# breadboard_rev04.net
KiCad netlist of a schematic drawn in EAGLE
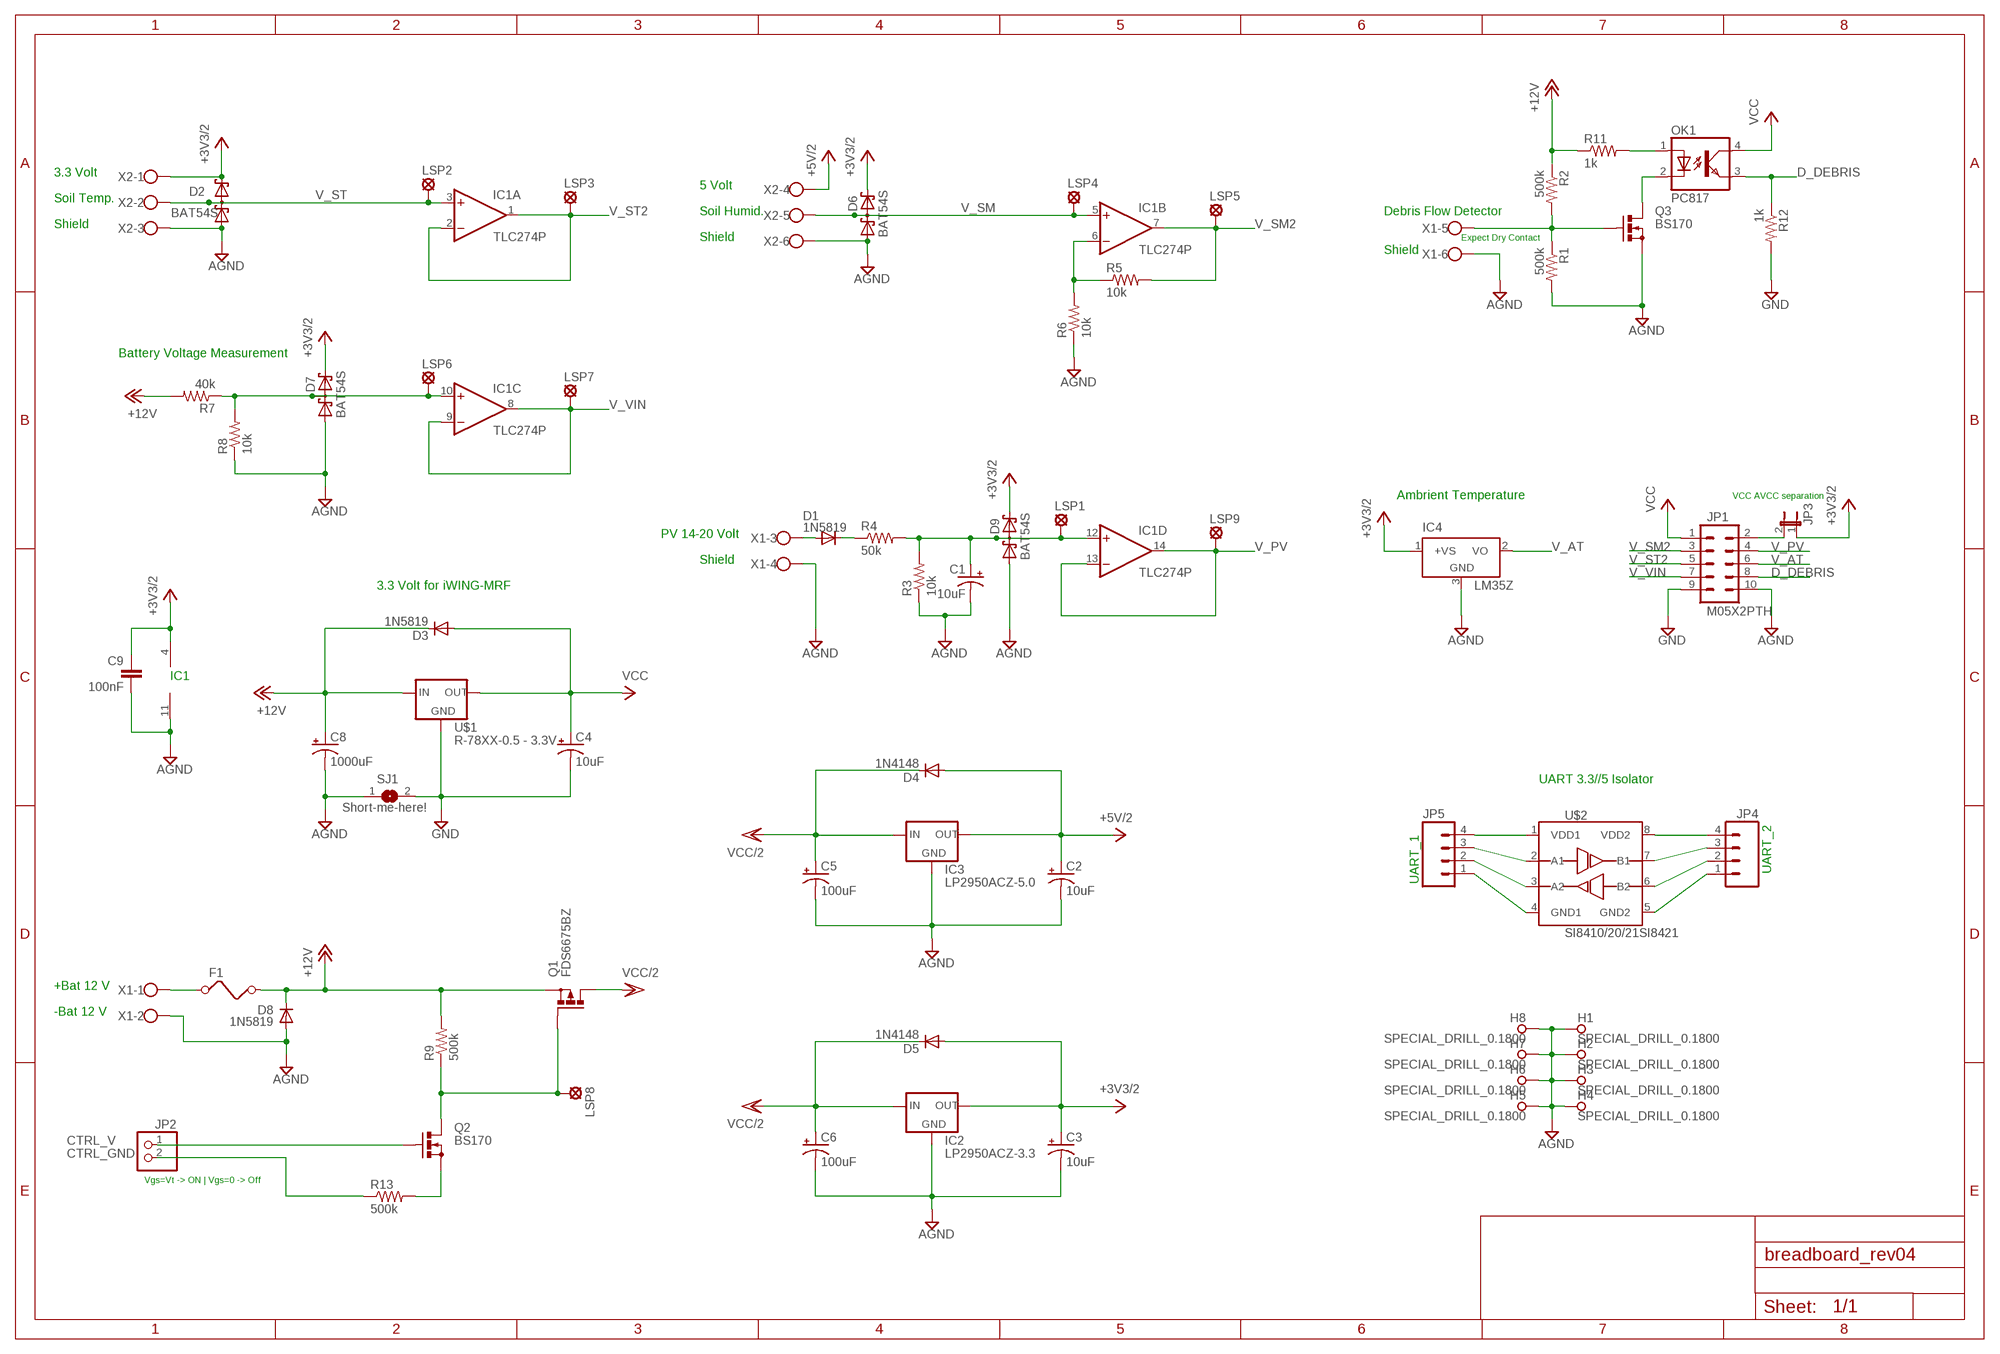
[diagram p0: schematic, sheet 1]

(export (version "E")
  (design (tool "Eeschema 10.0.6"))
  (components
    (comp (ref "C1")
      (value "10uF")
      (footprint "eagle-import:RCL_E2,5-7")
      (libsource (lib "eagle-import") (part "RCL_CPOL-USE2.5-7"))
    )
    (comp (ref "C2")
      (value "10uF")
      (footprint "eagle-import:RCL_E2,5-7")
      (libsource (lib "eagle-import") (part "RCL_CPOL-USE2.5-7"))
    )
    (comp (ref "C3")
      (value "10uF")
      (footprint "eagle-import:RCL_E2,5-7")
      (libsource (lib "eagle-import") (part "RCL_CPOL-USE2.5-7"))
    )
    (comp (ref "C4")
      (value "10uF")
      (footprint "eagle-import:RCL_E2,5-7")
      (libsource (lib "eagle-import") (part "RCL_CPOL-USE2.5-7"))
    )
    (comp (ref "C5")
      (value "100uF")
      (footprint "eagle-import:RCL_E2,5-7")
      (libsource (lib "eagle-import") (part "RCL_CPOL-USE2.5-7"))
    )
    (comp (ref "C6")
      (value "100uF")
      (footprint "eagle-import:RCL_E2,5-7")
      (libsource (lib "eagle-import") (part "RCL_CPOL-USE2.5-7"))
    )
    (comp (ref "C8")
      (value "1000uF")
      (footprint "eagle-import:RCL_E5-13")
      (libsource (lib "eagle-import") (part "RCL_CPOL-USE5-13"))
    )
    (comp (ref "C9")
      (value "100nF")
      (footprint "eagle-import:RCL_C050-025X075")
      (libsource (lib "eagle-import") (part "RCL_C-EU050-025X075"))
    )
    (comp (ref "D1")
      (value "1N5819")
      (footprint "eagle-import:DO41-10")
      (libsource (lib "eagle-import") (part "1N5819"))
    )
    (comp (ref "D2")
      (value "BAT54S")
      (footprint "eagle-import:SOT23")
      (libsource (lib "eagle-import") (part "BAT54S"))
    )
    (comp (ref "D3")
      (value "1N5819")
      (footprint "eagle-import:DO41-10")
      (libsource (lib "eagle-import") (part "1N5819"))
    )
    (comp (ref "D4")
      (value "1N4148")
      (footprint "eagle-import:DO35-10")
      (libsource (lib "eagle-import") (part "1N4148"))
    )
    (comp (ref "D5")
      (value "1N4148")
      (footprint "eagle-import:DO35-10")
      (libsource (lib "eagle-import") (part "1N4148"))
    )
    (comp (ref "D6")
      (value "BAT54S")
      (footprint "eagle-import:SOT23")
      (libsource (lib "eagle-import") (part "BAT54S"))
    )
    (comp (ref "D7")
      (value "BAT54S")
      (footprint "eagle-import:SOT23")
      (libsource (lib "eagle-import") (part "BAT54S"))
    )
    (comp (ref "D8")
      (value "1N5819")
      (footprint "eagle-import:DO41-10")
      (libsource (lib "eagle-import") (part "1N5819"))
    )
    (comp (ref "D9")
      (value "BAT54S")
      (footprint "eagle-import:SOT23")
      (libsource (lib "eagle-import") (part "BAT54S"))
    )
    (comp (ref "F1")
      (value "FUSE")
      (footprint "eagle-import:FUSE")
      (libsource (lib "eagle-import") (part "FUSE"))
    )
    (comp (ref "H1")
      (value "SPECIAL_DRILL_0.1800")
      (footprint "eagle-import:PAD_0.1800")
      (libsource (lib "eagle-import") (part "SPECIAL_DRILL_0.1800"))
    )
    (comp (ref "H2")
      (value "SPECIAL_DRILL_0.1800")
      (footprint "eagle-import:PAD_0.1800")
      (libsource (lib "eagle-import") (part "SPECIAL_DRILL_0.1800"))
    )
    (comp (ref "H3")
      (value "SPECIAL_DRILL_0.1800")
      (footprint "eagle-import:PAD_0.1800")
      (libsource (lib "eagle-import") (part "SPECIAL_DRILL_0.1800"))
    )
    (comp (ref "H4")
      (value "SPECIAL_DRILL_0.1800")
      (footprint "eagle-import:PAD_0.1800")
      (libsource (lib "eagle-import") (part "SPECIAL_DRILL_0.1800"))
    )
    (comp (ref "H5")
      (value "SPECIAL_DRILL_0.1800")
      (footprint "eagle-import:PAD_0.1800")
      (libsource (lib "eagle-import") (part "SPECIAL_DRILL_0.1800"))
    )
    (comp (ref "H6")
      (value "SPECIAL_DRILL_0.1800")
      (footprint "eagle-import:PAD_0.1800")
      (libsource (lib "eagle-import") (part "SPECIAL_DRILL_0.1800"))
    )
    (comp (ref "H7")
      (value "SPECIAL_DRILL_0.1800")
      (footprint "eagle-import:PAD_0.1800")
      (libsource (lib "eagle-import") (part "SPECIAL_DRILL_0.1800"))
    )
    (comp (ref "H8")
      (value "SPECIAL_DRILL_0.1800")
      (footprint "eagle-import:PAD_0.1800")
      (libsource (lib "eagle-import") (part "SPECIAL_DRILL_0.1800"))
    )
    (comp (ref "IC1")
      (value "TLC274P")
      (footprint "eagle-import:DIL14")
      (libsource (lib "eagle-import") (part "TLC274P"))
    )
    (comp (ref "IC2")
      (value "LP2950ACZ-3.3")
      (footprint "eagle-import:TO92")
      (libsource (lib "eagle-import") (part "LP2950?ACZ-3.3"))
    )
    (comp (ref "IC3")
      (value "LP2950ACZ-5.0")
      (footprint "eagle-import:TO92")
      (libsource (lib "eagle-import") (part "LP2950?ACZ-5.0"))
    )
    (comp (ref "IC4")
      (value "LM35Z")
      (footprint "eagle-import:TO92")
      (libsource (lib "eagle-import") (part "LM35?Z"))
    )
    (comp (ref "JP1")
      (value "M05X2PTH")
      (footprint "eagle-import:AVR_ICSP")
      (libsource (lib "eagle-import") (part "M05X2PTH"))
    )
    (comp (ref "JP2")
      (value "PINHD-1X2")
      (footprint "eagle-import:1X02")
      (libsource (lib "eagle-import") (part "PINHD-1X2"))
    )
    (comp (ref "JP3")
      (value "JP1E")
      (footprint "eagle-import:JUMPER_JP1")
      (libsource (lib "eagle-import") (part "JP1E"))
    )
    (comp (ref "JP4")
      (value "M04POLAR")
      (footprint "eagle-import:MOLEX-1X4")
      (libsource (lib "eagle-import") (part "M04POLAR"))
    )
    (comp (ref "JP5")
      (value "M04POLAR")
      (footprint "eagle-import:MOLEX-1X4")
      (libsource (lib "eagle-import") (part "M04POLAR"))
    )
    (comp (ref "LSP1")
      (value "LSP13")
      (footprint "eagle-import:LSP13")
      (libsource (lib "eagle-import") (part "LSP13"))
    )
    (comp (ref "LSP2")
      (value "LSP13")
      (footprint "eagle-import:LSP13")
      (libsource (lib "eagle-import") (part "LSP13"))
    )
    (comp (ref "LSP3")
      (value "LSP13")
      (footprint "eagle-import:LSP13")
      (libsource (lib "eagle-import") (part "LSP13"))
    )
    (comp (ref "LSP4")
      (value "LSP13")
      (footprint "eagle-import:LSP13")
      (libsource (lib "eagle-import") (part "LSP13"))
    )
    (comp (ref "LSP5")
      (value "LSP13")
      (footprint "eagle-import:LSP13")
      (libsource (lib "eagle-import") (part "LSP13"))
    )
    (comp (ref "LSP6")
      (value "LSP13")
      (footprint "eagle-import:LSP13")
      (libsource (lib "eagle-import") (part "LSP13"))
    )
    (comp (ref "LSP7")
      (value "LSP13")
      (footprint "eagle-import:LSP13")
      (libsource (lib "eagle-import") (part "LSP13"))
    )
    (comp (ref "LSP8")
      (value "LSP13")
      (footprint "eagle-import:LSP13")
      (libsource (lib "eagle-import") (part "LSP13"))
    )
    (comp (ref "LSP9")
      (value "LSP13")
      (footprint "eagle-import:LSP13")
      (libsource (lib "eagle-import") (part "LSP13"))
    )
    (comp (ref "OK1")
      (value "PC817")
      (footprint "eagle-import:DIL04")
      (fields (field (name "MPN") "PC817X4J000F"))
      (libsource (lib "eagle-import") (part "PC817"))
    )
    (comp (ref "Q1")
      (value "FDS6675BZ")
      (footprint "eagle-import:SO-08")
      (libsource (lib "eagle-import") (part "P-MOSFET-SO8"))
    )
    (comp (ref "Q2")
      (value "BS170")
      (footprint "eagle-import:SOT54E")
      (libsource (lib "eagle-import") (part "BS170"))
    )
    (comp (ref "Q3")
      (value "BS170")
      (footprint "eagle-import:SOT54E")
      (libsource (lib "eagle-import") (part "BS170"))
    )
    (comp (ref "R1")
      (value "500k")
      (footprint "eagle-import:RCL_0204_7")
      (libsource (lib "eagle-import") (part "RCL_R-US_0204/7"))
    )
    (comp (ref "R2")
      (value "500k")
      (footprint "eagle-import:RCL_0204_7")
      (libsource (lib "eagle-import") (part "RCL_R-US_0204/7"))
    )
    (comp (ref "R3")
      (value "10k")
      (footprint "eagle-import:RCL_0204_7")
      (libsource (lib "eagle-import") (part "RCL_R-US_0204/7"))
    )
    (comp (ref "R4")
      (value "50k")
      (footprint "eagle-import:RCL_0204_7")
      (libsource (lib "eagle-import") (part "RCL_R-US_0204/7"))
    )
    (comp (ref "R5")
      (value "10k")
      (footprint "eagle-import:RCL_0204_7")
      (libsource (lib "eagle-import") (part "RCL_R-US_0204/7"))
    )
    (comp (ref "R6")
      (value "10k")
      (footprint "eagle-import:RCL_0204_7")
      (libsource (lib "eagle-import") (part "RCL_R-US_0204/7"))
    )
    (comp (ref "R7")
      (value "40k")
      (footprint "eagle-import:RCL_0204_7")
      (libsource (lib "eagle-import") (part "RCL_R-US_0204/7"))
    )
    (comp (ref "R8")
      (value "10k")
      (footprint "eagle-import:RCL_0204_7")
      (libsource (lib "eagle-import") (part "RCL_R-US_0204/7"))
    )
    (comp (ref "R9")
      (value "500k")
      (footprint "eagle-import:RCL_0204_7")
      (libsource (lib "eagle-import") (part "RCL_R-US_0204/7"))
    )
    (comp (ref "R11")
      (value "1k")
      (footprint "eagle-import:RCL_0204_7")
      (libsource (lib "eagle-import") (part "RCL_R-US_0204/7"))
    )
    (comp (ref "R12")
      (value "1k")
      (footprint "eagle-import:RCL_0204_7")
      (libsource (lib "eagle-import") (part "RCL_R-US_0204/7"))
    )
    (comp (ref "R13")
      (value "500k")
      (footprint "eagle-import:RCL_0204_7")
      (libsource (lib "eagle-import") (part "RCL_R-US_0204/7"))
    )
    (comp (ref "SJ1")
      (value "Short-me-here!")
      (footprint "eagle-import:SJ")
      (libsource (lib "eagle-import") (part "SJ"))
    )
    (comp (ref "U$1")
      (value "R-78XX-0.5 - 3.3V")
      (footprint "eagle-import:SIP3")
      (libsource (lib "eagle-import") (part "R-78XX-0.5"))
    )
    (comp (ref "U$2")
      (value "SI8410/20/21SI8421")
      (footprint "eagle-import:SO-08")
      (libsource (lib "eagle-import") (part "SI8410/20/21SI8421"))
    )
    (comp (ref "X1")
      (value "5EHDRC-6P")
      (footprint "eagle-import:5EHDRC-6P")
      (libsource (lib "eagle-import") (part "5EHDRC-6P"))
    )
    (comp (ref "X2")
      (value "5EHDRC-6P")
      (footprint "eagle-import:5EHDRC-6P")
      (libsource (lib "eagle-import") (part "5EHDRC-6P"))
    )
  )
  (nets
    (net (code "1") (name "+3V3{slash}2") (class "Default")
      (node (ref "C3") (pin "+") (pinfunction "+_+") (pintype "passive"))
      (node (ref "C9") (pin "1") (pinfunction "1_1") (pintype "passive"))
      (node (ref "D2") (pin "3") (pinfunction "C2_3") (pintype "passive"))
      (node (ref "D5") (pin "A") (pinfunction "A_A") (pintype "passive"))
      (node (ref "D6") (pin "3") (pinfunction "C2_3") (pintype "passive"))
      (node (ref "D7") (pin "3") (pinfunction "C2_3") (pintype "passive"))
      (node (ref "D9") (pin "3") (pinfunction "C2_3") (pintype "passive"))
      (node (ref "IC1") (pin "4") (pinfunction "V+_4") (pintype "power_in"))
      (node (ref "IC2") (pin "1") (pinfunction "OUT_1") (pintype "passive"))
      (node (ref "IC4") (pin "1") (pinfunction "+VS_1") (pintype "input"))
      (node (ref "JP3") (pin "1") (pinfunction "1_1") (pintype "passive"))
      (node (ref "X2") (pin "1") (pinfunction "KL_1") (pintype "passive"))
    )
    (net (code "2") (name "+5V{slash}2") (class "Default")
      (node (ref "C2") (pin "+") (pinfunction "+_+") (pintype "passive"))
      (node (ref "D4") (pin "A") (pinfunction "A_A") (pintype "passive"))
      (node (ref "IC3") (pin "1") (pinfunction "OUT_1") (pintype "passive"))
      (node (ref "X2") (pin "4") (pinfunction "KL_4") (pintype "passive"))
    )
    (net (code "3") (name "+12V") (class "Default")
      (node (ref "C8") (pin "+") (pinfunction "+_+") (pintype "passive"))
      (node (ref "D3") (pin "C") (pinfunction "C_C") (pintype "passive"))
      (node (ref "D8") (pin "C") (pinfunction "C_C") (pintype "passive"))
      (node (ref "F1") (pin "2") (pinfunction "2_2") (pintype "passive"))
      (node (ref "Q1") (pin "1") (pinfunction "S_1") (pintype "passive"))
      (node (ref "Q1") (pin "2") (pinfunction "S_2") (pintype "passive"))
      (node (ref "Q1") (pin "3") (pinfunction "S_3") (pintype "passive"))
      (node (ref "R11") (pin "1") (pinfunction "1_1") (pintype "passive"))
      (node (ref "R2") (pin "1") (pinfunction "1_1") (pintype "passive"))
      (node (ref "R7") (pin "2") (pinfunction "2_2") (pintype "passive"))
      (node (ref "R9") (pin "2") (pinfunction "2_2") (pintype "passive"))
      (node (ref "U$1") (pin "1") (pinfunction "IN_1") (pintype "input"))
    )
    (net (code "4") (name "/CTRL_GND") (class "Default")
      (node (ref "JP2") (pin "2") (pinfunction "2_2") (pintype "passive"))
      (node (ref "R13") (pin "1") (pinfunction "1_1") (pintype "passive"))
    )
    (net (code "5") (name "/CTRL_V") (class "Default")
      (node (ref "JP2") (pin "1") (pinfunction "1_1") (pintype "passive"))
      (node (ref "Q2") (pin "G") (pinfunction "G_G") (pintype "passive"))
    )
    (net (code "6") (name "/D_DEBRIS") (class "Default")
      (node (ref "JP1") (pin "8") (pinfunction "8_8") (pintype "passive"))
      (node (ref "OK1") (pin "3") (pinfunction "EMIT_3") (pintype "passive"))
      (node (ref "R12") (pin "1") (pinfunction "1_1") (pintype "passive"))
    )
    (net (code "7") (name "/V_AT") (class "Default")
      (node (ref "IC4") (pin "2") (pinfunction "VO_2") (pintype "output"))
      (node (ref "JP1") (pin "6") (pinfunction "6_6") (pintype "passive"))
    )
    (net (code "8") (name "/V_PV") (class "Default")
      (node (ref "IC1") (pin "13") (pinfunction "-IN_13") (pintype "input"))
      (node (ref "IC1") (pin "14") (pinfunction "OUT_14") (pintype "output"))
      (node (ref "JP1") (pin "4") (pinfunction "4_4") (pintype "passive"))
      (node (ref "LSP9") (pin "MP") (pinfunction "MP_MP") (pintype "passive"))
    )
    (net (code "9") (name "/V_SM") (class "Default")
      (node (ref "D6") (pin "2") (pinfunction "C1A2_2") (pintype "passive"))
      (node (ref "IC1") (pin "5") (pinfunction "+IN_5") (pintype "input"))
      (node (ref "LSP4") (pin "MP") (pinfunction "MP_MP") (pintype "passive"))
      (node (ref "X2") (pin "5") (pinfunction "KL_5") (pintype "passive"))
    )
    (net (code "10") (name "/V_SM2") (class "Default")
      (node (ref "IC1") (pin "7") (pinfunction "OUT_7") (pintype "output"))
      (node (ref "JP1") (pin "3") (pinfunction "3_3") (pintype "passive"))
      (node (ref "LSP5") (pin "MP") (pinfunction "MP_MP") (pintype "passive"))
      (node (ref "R5") (pin "2") (pinfunction "2_2") (pintype "passive"))
    )
    (net (code "11") (name "/V_ST") (class "Default")
      (node (ref "D2") (pin "2") (pinfunction "C1A2_2") (pintype "passive"))
      (node (ref "IC1") (pin "3") (pinfunction "+IN_3") (pintype "input"))
      (node (ref "LSP2") (pin "MP") (pinfunction "MP_MP") (pintype "passive"))
      (node (ref "X2") (pin "2") (pinfunction "KL_2") (pintype "passive"))
    )
    (net (code "12") (name "/V_ST2") (class "Default")
      (node (ref "IC1") (pin "1") (pinfunction "OUT_1") (pintype "output"))
      (node (ref "IC1") (pin "2") (pinfunction "-IN_2") (pintype "input"))
      (node (ref "JP1") (pin "5") (pinfunction "5_5") (pintype "passive"))
      (node (ref "LSP3") (pin "MP") (pinfunction "MP_MP") (pintype "passive"))
    )
    (net (code "13") (name "/V_VIN") (class "Default")
      (node (ref "IC1") (pin "8") (pinfunction "OUT_8") (pintype "output"))
      (node (ref "IC1") (pin "9") (pinfunction "-IN_9") (pintype "input"))
      (node (ref "JP1") (pin "7") (pinfunction "7_7") (pintype "passive"))
      (node (ref "LSP7") (pin "MP") (pinfunction "MP_MP") (pintype "passive"))
    )
    (net (code "14") (name "AGND") (class "Default")
      (node (ref "C1") (pin "-") (pinfunction "-_-") (pintype "passive"))
      (node (ref "C2") (pin "-") (pinfunction "-_-") (pintype "passive"))
      (node (ref "C3") (pin "-") (pinfunction "-_-") (pintype "passive"))
      (node (ref "C5") (pin "-") (pinfunction "-_-") (pintype "passive"))
      (node (ref "C6") (pin "-") (pinfunction "-_-") (pintype "passive"))
      (node (ref "C8") (pin "-") (pinfunction "-_-") (pintype "passive"))
      (node (ref "C9") (pin "2") (pinfunction "2_2") (pintype "passive"))
      (node (ref "D2") (pin "1") (pinfunction "A1_1") (pintype "passive"))
      (node (ref "D6") (pin "1") (pinfunction "A1_1") (pintype "passive"))
      (node (ref "D7") (pin "1") (pinfunction "A1_1") (pintype "passive"))
      (node (ref "D8") (pin "A") (pinfunction "A_A") (pintype "passive"))
      (node (ref "D9") (pin "1") (pinfunction "A1_1") (pintype "passive"))
      (node (ref "H1") (pin "1") (pinfunction "1_1") (pintype "passive"))
      (node (ref "H2") (pin "1") (pinfunction "1_1") (pintype "passive"))
      (node (ref "H3") (pin "1") (pinfunction "1_1") (pintype "passive"))
      (node (ref "H4") (pin "1") (pinfunction "1_1") (pintype "passive"))
      (node (ref "H5") (pin "1") (pinfunction "1_1") (pintype "passive"))
      (node (ref "H6") (pin "1") (pinfunction "1_1") (pintype "passive"))
      (node (ref "H7") (pin "1") (pinfunction "1_1") (pintype "passive"))
      (node (ref "H8") (pin "1") (pinfunction "1_1") (pintype "passive"))
      (node (ref "IC1") (pin "11") (pinfunction "V-_11") (pintype "power_in"))
      (node (ref "IC2") (pin "2") (pinfunction "GND_2") (pintype "input"))
      (node (ref "IC3") (pin "2") (pinfunction "GND_2") (pintype "input"))
      (node (ref "IC4") (pin "3") (pinfunction "GND_3") (pintype "power_in"))
      (node (ref "JP1") (pin "10") (pinfunction "10_10") (pintype "passive"))
      (node (ref "Q3") (pin "S") (pinfunction "S_S") (pintype "passive"))
      (node (ref "R1") (pin "2") (pinfunction "2_2") (pintype "passive"))
      (node (ref "R3") (pin "1") (pinfunction "1_1") (pintype "passive"))
      (node (ref "R6") (pin "1") (pinfunction "1_1") (pintype "passive"))
      (node (ref "R8") (pin "1") (pinfunction "1_1") (pintype "passive"))
      (node (ref "SJ1") (pin "1") (pinfunction "1_1") (pintype "passive"))
      (node (ref "X1") (pin "2") (pinfunction "KL_2") (pintype "passive"))
      (node (ref "X1") (pin "4") (pinfunction "KL_4") (pintype "passive"))
      (node (ref "X1") (pin "6") (pinfunction "KL_6") (pintype "passive"))
      (node (ref "X2") (pin "3") (pinfunction "KL_3") (pintype "passive"))
      (node (ref "X2") (pin "6") (pinfunction "KL_6") (pintype "passive"))
    )
    (net (code "15") (name "GND") (class "Default")
      (node (ref "C4") (pin "-") (pinfunction "-_-") (pintype "passive"))
      (node (ref "JP1") (pin "9") (pinfunction "9_9") (pintype "passive"))
      (node (ref "R12") (pin "2") (pinfunction "2_2") (pintype "passive"))
      (node (ref "SJ1") (pin "2") (pinfunction "2_2") (pintype "passive"))
      (node (ref "U$1") (pin "2") (pinfunction "GND_2") (pintype "input"))
    )
    (net (code "16") (name "Net-(D1-PadC)") (class "Default")
      (node (ref "D1") (pin "C") (pinfunction "C_C") (pintype "passive"))
      (node (ref "R4") (pin "1") (pinfunction "1_1") (pintype "passive"))
    )
    (net (code "17") (name "Net-(D7-C1A2)") (class "Default")
      (node (ref "D7") (pin "2") (pinfunction "C1A2_2") (pintype "passive"))
      (node (ref "IC1") (pin "10") (pinfunction "+IN_10") (pintype "input"))
      (node (ref "LSP6") (pin "MP") (pinfunction "MP_MP") (pintype "passive"))
      (node (ref "R7") (pin "1") (pinfunction "1_1") (pintype "passive"))
      (node (ref "R8") (pin "2") (pinfunction "2_2") (pintype "passive"))
    )
    (net (code "18") (name "Net-(D9-C1A2)") (class "Default")
      (node (ref "C1") (pin "+") (pinfunction "+_+") (pintype "passive"))
      (node (ref "D9") (pin "2") (pinfunction "C1A2_2") (pintype "passive"))
      (node (ref "IC1") (pin "12") (pinfunction "+IN_12") (pintype "input"))
      (node (ref "LSP1") (pin "MP") (pinfunction "MP_MP") (pintype "passive"))
      (node (ref "R3") (pin "2") (pinfunction "2_2") (pintype "passive"))
      (node (ref "R4") (pin "2") (pinfunction "2_2") (pintype "passive"))
    )
    (net (code "19") (name "Net-(IC1B--IN)") (class "Default")
      (node (ref "IC1") (pin "6") (pinfunction "-IN_6") (pintype "input"))
      (node (ref "R5") (pin "1") (pinfunction "1_1") (pintype "passive"))
      (node (ref "R6") (pin "2") (pinfunction "2_2") (pintype "passive"))
    )
    (net (code "20") (name "Net-(JP1-Pad2)") (class "Default")
      (node (ref "JP1") (pin "2") (pinfunction "2_2") (pintype "passive"))
      (node (ref "JP3") (pin "2") (pinfunction "2_2") (pintype "passive"))
    )
    (net (code "21") (name "Net-(OK1-A)") (class "Default")
      (node (ref "OK1") (pin "1") (pinfunction "A_1") (pintype "passive"))
      (node (ref "R11") (pin "2") (pinfunction "2_2") (pintype "passive"))
    )
    (net (code "22") (name "Net-(OK1-C)") (class "Default")
      (node (ref "OK1") (pin "2") (pinfunction "C_2") (pintype "passive"))
      (node (ref "Q3") (pin "D") (pinfunction "D_D") (pintype "passive"))
    )
    (net (code "23") (name "Net-(Q1-G)") (class "Default")
      (node (ref "LSP8") (pin "MP") (pinfunction "MP_MP") (pintype "passive"))
      (node (ref "Q1") (pin "4") (pinfunction "G_4") (pintype "passive"))
      (node (ref "Q2") (pin "D") (pinfunction "D_D") (pintype "passive"))
      (node (ref "R9") (pin "1") (pinfunction "1_1") (pintype "passive"))
    )
    (net (code "24") (name "Net-(Q2-PadS)") (class "Default")
      (node (ref "Q2") (pin "S") (pinfunction "S_S") (pintype "passive"))
      (node (ref "R13") (pin "2") (pinfunction "2_2") (pintype "passive"))
    )
    (net (code "25") (name "Net-(U$2-A1)") (class "Default")
      (node (ref "JP5") (pin "3") (pinfunction "3_3") (pintype "passive"))
      (node (ref "U$2") (pin "2") (pinfunction "A1_2") (pintype "input"))
    )
    (net (code "26") (name "Net-(U$2-A2)") (class "Default")
      (node (ref "JP5") (pin "2") (pinfunction "2_2") (pintype "passive"))
      (node (ref "U$2") (pin "3") (pinfunction "A2_3") (pintype "output"))
    )
    (net (code "27") (name "Net-(U$2-B1)") (class "Default")
      (node (ref "JP4") (pin "3") (pinfunction "3_3") (pintype "passive"))
      (node (ref "U$2") (pin "7") (pinfunction "B1_7") (pintype "output"))
    )
    (net (code "28") (name "Net-(U$2-B2)") (class "Default")
      (node (ref "JP4") (pin "2") (pinfunction "2_2") (pintype "passive"))
      (node (ref "U$2") (pin "6") (pinfunction "B2_6") (pintype "input"))
    )
    (net (code "29") (name "Net-(U$2-GND1)") (class "Default")
      (node (ref "JP5") (pin "1") (pinfunction "1_1") (pintype "passive"))
      (node (ref "U$2") (pin "4") (pinfunction "GND1_4") (pintype "power_in"))
    )
    (net (code "30") (name "Net-(U$2-GND2)") (class "Default")
      (node (ref "JP4") (pin "1") (pinfunction "1_1") (pintype "passive"))
      (node (ref "U$2") (pin "5") (pinfunction "GND2_5") (pintype "power_in"))
    )
    (net (code "31") (name "Net-(U$2-VDD1)") (class "Default")
      (node (ref "JP5") (pin "4") (pinfunction "4_4") (pintype "passive"))
      (node (ref "U$2") (pin "1") (pinfunction "VDD1_1") (pintype "power_in"))
    )
    (net (code "32") (name "Net-(U$2-VDD2)") (class "Default")
      (node (ref "JP4") (pin "4") (pinfunction "4_4") (pintype "passive"))
      (node (ref "U$2") (pin "8") (pinfunction "VDD2_8") (pintype "power_in"))
    )
    (net (code "33") (name "Net-(X1A-KL)") (class "Default")
      (node (ref "F1") (pin "1") (pinfunction "1_1") (pintype "passive"))
      (node (ref "X1") (pin "1") (pinfunction "KL_1") (pintype "passive"))
    )
    (net (code "34") (name "Net-(X1C-KL)") (class "Default")
      (node (ref "D1") (pin "A") (pinfunction "A_A") (pintype "passive"))
      (node (ref "X1") (pin "3") (pinfunction "KL_3") (pintype "passive"))
    )
    (net (code "35") (name "Net-(X1E-KL)") (class "Default")
      (node (ref "Q3") (pin "G") (pinfunction "G_G") (pintype "passive"))
      (node (ref "R1") (pin "1") (pinfunction "1_1") (pintype "passive"))
      (node (ref "R2") (pin "2") (pinfunction "2_2") (pintype "passive"))
      (node (ref "X1") (pin "5") (pinfunction "KL_5") (pintype "passive"))
    )
    (net (code "36") (name "VCC") (class "Default")
      (node (ref "C4") (pin "+") (pinfunction "+_+") (pintype "passive"))
      (node (ref "D3") (pin "A") (pinfunction "A_A") (pintype "passive"))
      (node (ref "JP1") (pin "1") (pinfunction "1_1") (pintype "passive"))
      (node (ref "OK1") (pin "4") (pinfunction "COL_4") (pintype "passive"))
      (node (ref "U$1") (pin "3") (pinfunction "OUT_3") (pintype "passive"))
    )
    (net (code "37") (name "VCC{slash}2") (class "Default")
      (node (ref "C5") (pin "+") (pinfunction "+_+") (pintype "passive"))
      (node (ref "C6") (pin "+") (pinfunction "+_+") (pintype "passive"))
      (node (ref "D4") (pin "C") (pinfunction "C_C") (pintype "passive"))
      (node (ref "D5") (pin "C") (pinfunction "C_C") (pintype "passive"))
      (node (ref "IC2") (pin "3") (pinfunction "IN_3") (pintype "input"))
      (node (ref "IC3") (pin "3") (pinfunction "IN_3") (pintype "input"))
      (node (ref "Q1") (pin "5") (pinfunction "D_5") (pintype "passive"))
      (node (ref "Q1") (pin "6") (pinfunction "D_6") (pintype "passive"))
      (node (ref "Q1") (pin "7") (pinfunction "D_7") (pintype "passive"))
      (node (ref "Q1") (pin "8") (pinfunction "D_8") (pintype "passive"))
    )
  )
)
